# Leds.net
KiCad netlist of a schematic drawn in Altium Designer
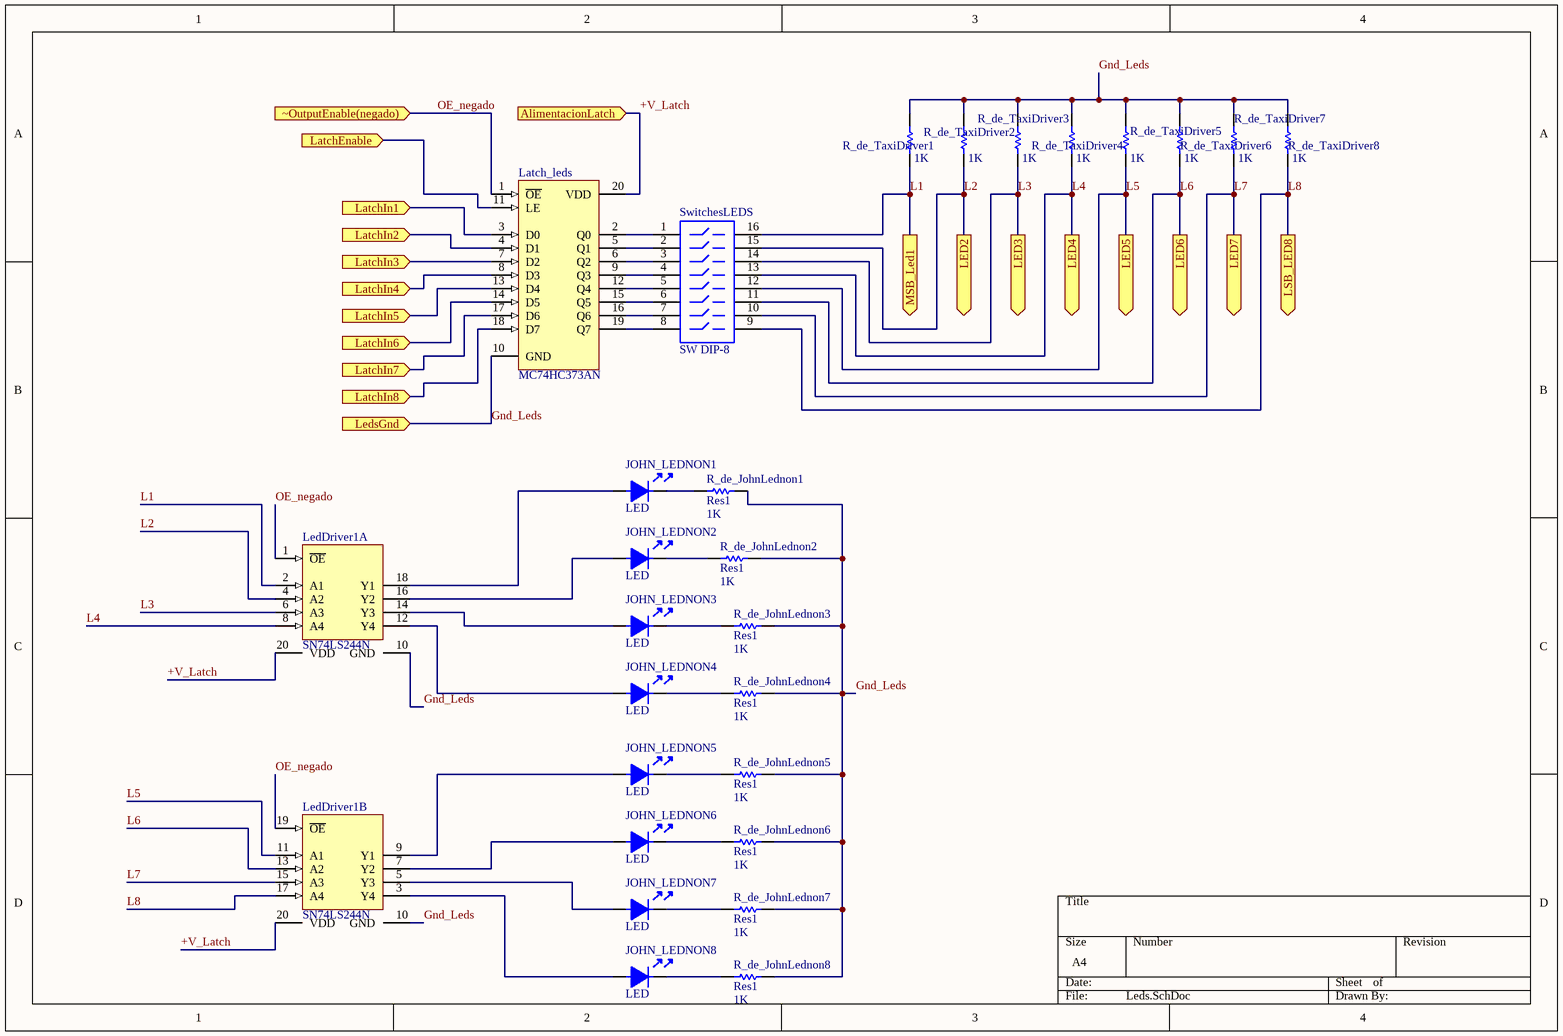
[diagram p0: Leds.SchDoc]

(export (version "E")
  (design (tool "Eeschema 10.0.6"))
  (components
    (comp (ref "JOHN_LEDNON1") (value "LED") (footprint "LED3") (libsource (lib "LIBEBAL") (part "LED")))
    (comp (ref "JOHN_LEDNON2") (value "LED") (footprint "LED3") (libsource (lib "LIBEBAL") (part "LED")))
    (comp (ref "JOHN_LEDNON3") (value "LED") (footprint "LED3") (libsource (lib "LIBEBAL") (part "LED")))
    (comp (ref "JOHN_LEDNON4") (value "LED") (footprint "LED3") (libsource (lib "LIBEBAL") (part "LED")))
    (comp (ref "JOHN_LEDNON5") (value "LED") (footprint "LED3") (libsource (lib "LIBEBAL") (part "LED")))
    (comp (ref "JOHN_LEDNON6") (value "LED") (footprint "LED3") (libsource (lib "LIBEBAL") (part "LED")))
    (comp (ref "JOHN_LEDNON7") (value "LED") (footprint "LED3") (libsource (lib "LIBEBAL") (part "LED")))
    (comp (ref "JOHN_LEDNON8") (value "LED") (footprint "LED3") (libsource (lib "LIBEBAL") (part "LED")))
    (comp (ref "Latch_leds")
      (value "MC74HC373AN")
      (footprint "738-03")
      (description "Octal 3-State Non-Inverting Transparent Latch")
      (fields (field (name "PUBLISHER") "Altium Limited"))
      (libsource (lib "ON Semi Logic Latch") (part "MC74HC373AN"))
    )
    (comp (ref "LedDriver1")
      (value "SN74LS244N")
      (footprint "738-03")
      (description "Octal Buffer/Line Driver with 3-State Outputs")
      (fields (field (name "PUBLISHER") "Altium Limited"))
      (libsource (lib "ON Semi Logic Buffer Line Driver") (part "SN74LS244N"))
    )
    (comp (ref "R_de_JohnLednon1")
      (value "Res1")
      (footprint "AXIAL-0.3")
      (description "Resistor")
      (fields (field (name "ALTIUM_VALUE") "1K") (field (name "PUBLISHER") "Altium Limited"))
      (libsource (lib "Miscellaneous Devices") (part "Res1"))
    )
    (comp (ref "R_de_JohnLednon2")
      (value "Res1")
      (footprint "AXIAL-0.3")
      (description "Resistor")
      (fields (field (name "ALTIUM_VALUE") "1K") (field (name "PUBLISHER") "Altium Limited"))
      (libsource (lib "Miscellaneous Devices") (part "Res1"))
    )
    (comp (ref "R_de_JohnLednon3")
      (value "Res1")
      (footprint "AXIAL-0.3")
      (description "Resistor")
      (fields (field (name "ALTIUM_VALUE") "1K") (field (name "PUBLISHER") "Altium Limited"))
      (libsource (lib "Miscellaneous Devices") (part "Res1"))
    )
    (comp (ref "R_de_JohnLednon4")
      (value "Res1")
      (footprint "AXIAL-0.3")
      (description "Resistor")
      (fields (field (name "ALTIUM_VALUE") "1K") (field (name "PUBLISHER") "Altium Limited"))
      (libsource (lib "Miscellaneous Devices") (part "Res1"))
    )
    (comp (ref "R_de_JohnLednon5")
      (value "Res1")
      (footprint "AXIAL-0.3")
      (description "Resistor")
      (fields (field (name "ALTIUM_VALUE") "1K") (field (name "PUBLISHER") "Altium Limited"))
      (libsource (lib "Miscellaneous Devices") (part "Res1"))
    )
    (comp (ref "R_de_JohnLednon6")
      (value "Res1")
      (footprint "AXIAL-0.3")
      (description "Resistor")
      (fields (field (name "ALTIUM_VALUE") "1K") (field (name "PUBLISHER") "Altium Limited"))
      (libsource (lib "Miscellaneous Devices") (part "Res1"))
    )
    (comp (ref "R_de_JohnLednon7")
      (value "Res1")
      (footprint "AXIAL-0.3")
      (description "Resistor")
      (fields (field (name "ALTIUM_VALUE") "1K") (field (name "PUBLISHER") "Altium Limited"))
      (libsource (lib "Miscellaneous Devices") (part "Res1"))
    )
    (comp (ref "R_de_JohnLednon8")
      (value "Res1")
      (footprint "AXIAL-0.3")
      (description "Resistor")
      (fields (field (name "ALTIUM_VALUE") "1K") (field (name "PUBLISHER") "Altium Limited"))
      (libsource (lib "Miscellaneous Devices") (part "Res1"))
    )
    (comp (ref "R_de_TaxiDriver1")
      (value "1K")
      (footprint "AXIAL-0.3")
      (description "Resistor")
      (fields (field (name "Comment") "Res1") (field (name "PUBLISHER") "Altium Limited"))
      (libsource (lib "Miscellaneous Devices") (part "Res1"))
    )
    (comp (ref "R_de_TaxiDriver2")
      (value "1K")
      (footprint "AXIAL-0.3")
      (description "Resistor")
      (fields (field (name "Comment") "Res1") (field (name "PUBLISHER") "Altium Limited"))
      (libsource (lib "Miscellaneous Devices") (part "Res1"))
    )
    (comp (ref "R_de_TaxiDriver3")
      (value "1K")
      (footprint "AXIAL-0.3")
      (description "Resistor")
      (fields (field (name "Comment") "Res1") (field (name "PUBLISHER") "Altium Limited"))
      (libsource (lib "Miscellaneous Devices") (part "Res1"))
    )
    (comp (ref "R_de_TaxiDriver4")
      (value "1K")
      (footprint "AXIAL-0.3")
      (description "Resistor")
      (fields (field (name "Comment") "Res1") (field (name "PUBLISHER") "Altium Limited"))
      (libsource (lib "Miscellaneous Devices") (part "Res1"))
    )
    (comp (ref "R_de_TaxiDriver5")
      (value "1K")
      (footprint "AXIAL-0.3")
      (description "Resistor")
      (fields (field (name "Comment") "Res1") (field (name "PUBLISHER") "Altium Limited"))
      (libsource (lib "Miscellaneous Devices") (part "Res1"))
    )
    (comp (ref "R_de_TaxiDriver6")
      (value "1K")
      (footprint "AXIAL-0.3")
      (description "Resistor")
      (fields (field (name "Comment") "Res1") (field (name "PUBLISHER") "Altium Limited"))
      (libsource (lib "Miscellaneous Devices") (part "Res1"))
    )
    (comp (ref "R_de_TaxiDriver7")
      (value "1K")
      (footprint "AXIAL-0.3")
      (description "Resistor")
      (fields (field (name "Comment") "Res1") (field (name "PUBLISHER") "Altium Limited"))
      (libsource (lib "Miscellaneous Devices") (part "Res1"))
    )
    (comp (ref "R_de_TaxiDriver8")
      (value "1K")
      (footprint "AXIAL-0.3")
      (description "Resistor")
      (fields (field (name "Comment") "Res1") (field (name "PUBLISHER") "Altium Limited"))
      (libsource (lib "Miscellaneous Devices") (part "Res1"))
    )
    (comp (ref "SwitchesLEDS")
      (value "SW DIP-8")
      (footprint "DIP-16-KEY")
      (description "4009 Series DIP Switch, Raised actuator")
      (fields (field (name "PUBLISHER") "Altium Limited"))
      (libsource (lib "Miscellaneous Devices") (part "SW-DIP8"))
    )
  )
  (nets
    (net (code "1") (name "/L1") (class "Default")
      (node (ref "LedDriver1") (pin "2") (pinfunction "A1_2") (pintype "input"))
      (node (ref "R_de_TaxiDriver1") (pin "1") (pinfunction "1_1") (pintype "passive"))
      (node (ref "SwitchesLEDS") (pin "16") (pinfunction "16_16") (pintype "passive"))
    )
    (net (code "2") (name "/L2") (class "Default")
      (node (ref "LedDriver1") (pin "4") (pinfunction "A2_4") (pintype "input"))
      (node (ref "R_de_TaxiDriver2") (pin "1") (pinfunction "1_1") (pintype "passive"))
      (node (ref "SwitchesLEDS") (pin "15") (pinfunction "15_15") (pintype "passive"))
    )
    (net (code "3") (name "/L3") (class "Default")
      (node (ref "LedDriver1") (pin "6") (pinfunction "A3_6") (pintype "input"))
      (node (ref "R_de_TaxiDriver3") (pin "1") (pinfunction "1_1") (pintype "passive"))
      (node (ref "SwitchesLEDS") (pin "14") (pinfunction "14_14") (pintype "passive"))
    )
    (net (code "4") (name "/L4") (class "Default")
      (node (ref "LedDriver1") (pin "8") (pinfunction "A4_8") (pintype "input"))
      (node (ref "R_de_TaxiDriver4") (pin "1") (pinfunction "1_1") (pintype "passive"))
      (node (ref "SwitchesLEDS") (pin "13") (pinfunction "13_13") (pintype "passive"))
    )
    (net (code "5") (name "/L5") (class "Default")
      (node (ref "LedDriver1") (pin "11") (pinfunction "A1_11") (pintype "input"))
      (node (ref "R_de_TaxiDriver5") (pin "1") (pinfunction "1_1") (pintype "passive"))
      (node (ref "SwitchesLEDS") (pin "12") (pinfunction "12_12") (pintype "passive"))
    )
    (net (code "6") (name "/L6") (class "Default")
      (node (ref "LedDriver1") (pin "13") (pinfunction "A2_13") (pintype "input"))
      (node (ref "R_de_TaxiDriver6") (pin "1") (pinfunction "1_1") (pintype "passive"))
      (node (ref "SwitchesLEDS") (pin "11") (pinfunction "11_11") (pintype "passive"))
    )
    (net (code "7") (name "/L7") (class "Default")
      (node (ref "LedDriver1") (pin "15") (pinfunction "A3_15") (pintype "input"))
      (node (ref "R_de_TaxiDriver7") (pin "1") (pinfunction "1_1") (pintype "passive"))
      (node (ref "SwitchesLEDS") (pin "10") (pinfunction "10_10") (pintype "passive"))
    )
    (net (code "8") (name "/L8") (class "Default")
      (node (ref "LedDriver1") (pin "17") (pinfunction "A4_17") (pintype "input"))
      (node (ref "R_de_TaxiDriver8") (pin "1") (pinfunction "1_1") (pintype "passive"))
      (node (ref "SwitchesLEDS") (pin "9") (pinfunction "9_9") (pintype "passive"))
    )
    (net (code "9") (name "/LatchEnable") (class "Default")
      (node (ref "Latch_leds") (pin "11") (pinfunction "LE_11") (pintype "input"))
    )
    (net (code "10") (name "/LatchIn1") (class "Default")
      (node (ref "Latch_leds") (pin "3") (pinfunction "D0_3") (pintype "input"))
    )
    (net (code "11") (name "/LatchIn2") (class "Default")
      (node (ref "Latch_leds") (pin "4") (pinfunction "D1_4") (pintype "input"))
    )
    (net (code "12") (name "/LatchIn3") (class "Default")
      (node (ref "Latch_leds") (pin "7") (pinfunction "D2_7") (pintype "input"))
    )
    (net (code "13") (name "/LatchIn4") (class "Default")
      (node (ref "Latch_leds") (pin "8") (pinfunction "D3_8") (pintype "input"))
    )
    (net (code "14") (name "/LatchIn5") (class "Default")
      (node (ref "Latch_leds") (pin "13") (pinfunction "D4_13") (pintype "input"))
    )
    (net (code "15") (name "/LatchIn6") (class "Default")
      (node (ref "Latch_leds") (pin "14") (pinfunction "D5_14") (pintype "input"))
    )
    (net (code "16") (name "/LatchIn7") (class "Default")
      (node (ref "Latch_leds") (pin "17") (pinfunction "D6_17") (pintype "input"))
    )
    (net (code "17") (name "/LatchIn8") (class "Default")
      (node (ref "Latch_leds") (pin "18") (pinfunction "D7_18") (pintype "input"))
    )
    (net (code "18") (name "/OE_negado") (class "Default")
      (node (ref "Latch_leds") (pin "1") (pinfunction "~{OE}_1") (pintype "input"))
      (node (ref "LedDriver1") (pin "1") (pinfunction "~{OE}_1") (pintype "input"))
      (node (ref "LedDriver1") (pin "19") (pinfunction "~{OE}_19") (pintype "input"))
    )
    (net (code "19") (name "GND") (class "Default")
      (node (ref "Latch_leds") (pin "10") (pinfunction "GND_10") (pintype "power_in"))
      (node (ref "LedDriver1") (pin "10") (pinfunction "GND_10") (pintype "power_in"))
      (node (ref "R_de_JohnLednon1") (pin "2") (pinfunction "2_2") (pintype "passive"))
      (node (ref "R_de_JohnLednon2") (pin "2") (pinfunction "2_2") (pintype "passive"))
      (node (ref "R_de_JohnLednon3") (pin "2") (pinfunction "2_2") (pintype "passive"))
      (node (ref "R_de_JohnLednon4") (pin "2") (pinfunction "2_2") (pintype "passive"))
      (node (ref "R_de_JohnLednon5") (pin "2") (pinfunction "2_2") (pintype "passive"))
      (node (ref "R_de_JohnLednon6") (pin "2") (pinfunction "2_2") (pintype "passive"))
      (node (ref "R_de_JohnLednon7") (pin "2") (pinfunction "2_2") (pintype "passive"))
      (node (ref "R_de_JohnLednon8") (pin "2") (pinfunction "2_2") (pintype "passive"))
      (node (ref "R_de_TaxiDriver1") (pin "2") (pinfunction "2_2") (pintype "passive"))
      (node (ref "R_de_TaxiDriver2") (pin "2") (pinfunction "2_2") (pintype "passive"))
      (node (ref "R_de_TaxiDriver3") (pin "2") (pinfunction "2_2") (pintype "passive"))
      (node (ref "R_de_TaxiDriver4") (pin "2") (pinfunction "2_2") (pintype "passive"))
      (node (ref "R_de_TaxiDriver5") (pin "2") (pinfunction "2_2") (pintype "passive"))
      (node (ref "R_de_TaxiDriver6") (pin "2") (pinfunction "2_2") (pintype "passive"))
      (node (ref "R_de_TaxiDriver7") (pin "2") (pinfunction "2_2") (pintype "passive"))
      (node (ref "R_de_TaxiDriver8") (pin "2") (pinfunction "2_2") (pintype "passive"))
    )
    (net (code "20") (name "Net-(JOHN_LEDNON1-Pad2)") (class "Default")
      (node (ref "JOHN_LEDNON1") (pin "2") (pinfunction "2_2") (pintype "passive"))
      (node (ref "R_de_JohnLednon1") (pin "1") (pinfunction "1_1") (pintype "passive"))
    )
    (net (code "21") (name "Net-(JOHN_LEDNON2-Pad2)") (class "Default")
      (node (ref "JOHN_LEDNON2") (pin "2") (pinfunction "2_2") (pintype "passive"))
      (node (ref "R_de_JohnLednon2") (pin "1") (pinfunction "1_1") (pintype "passive"))
    )
    (net (code "22") (name "Net-(JOHN_LEDNON3-Pad2)") (class "Default")
      (node (ref "JOHN_LEDNON3") (pin "2") (pinfunction "2_2") (pintype "passive"))
      (node (ref "R_de_JohnLednon3") (pin "1") (pinfunction "1_1") (pintype "passive"))
    )
    (net (code "23") (name "Net-(JOHN_LEDNON4-Pad2)") (class "Default")
      (node (ref "JOHN_LEDNON4") (pin "2") (pinfunction "2_2") (pintype "passive"))
      (node (ref "R_de_JohnLednon4") (pin "1") (pinfunction "1_1") (pintype "passive"))
    )
    (net (code "24") (name "Net-(JOHN_LEDNON5-Pad2)") (class "Default")
      (node (ref "JOHN_LEDNON5") (pin "2") (pinfunction "2_2") (pintype "passive"))
      (node (ref "R_de_JohnLednon5") (pin "1") (pinfunction "1_1") (pintype "passive"))
    )
    (net (code "25") (name "Net-(JOHN_LEDNON6-Pad2)") (class "Default")
      (node (ref "JOHN_LEDNON6") (pin "2") (pinfunction "2_2") (pintype "passive"))
      (node (ref "R_de_JohnLednon6") (pin "1") (pinfunction "1_1") (pintype "passive"))
    )
    (net (code "26") (name "Net-(JOHN_LEDNON7-Pad2)") (class "Default")
      (node (ref "JOHN_LEDNON7") (pin "2") (pinfunction "2_2") (pintype "passive"))
      (node (ref "R_de_JohnLednon7") (pin "1") (pinfunction "1_1") (pintype "passive"))
    )
    (net (code "27") (name "Net-(JOHN_LEDNON8-Pad2)") (class "Default")
      (node (ref "JOHN_LEDNON8") (pin "2") (pinfunction "2_2") (pintype "passive"))
      (node (ref "R_de_JohnLednon8") (pin "1") (pinfunction "1_1") (pintype "passive"))
    )
    (net (code "28") (name "Net-(Latch_leds-Q0)") (class "Default")
      (node (ref "Latch_leds") (pin "2") (pinfunction "Q0_2") (pintype "tri_state"))
      (node (ref "SwitchesLEDS") (pin "1") (pinfunction "1_1") (pintype "passive"))
    )
    (net (code "29") (name "Net-(Latch_leds-Q1)") (class "Default")
      (node (ref "Latch_leds") (pin "5") (pinfunction "Q1_5") (pintype "tri_state"))
      (node (ref "SwitchesLEDS") (pin "2") (pinfunction "2_2") (pintype "passive"))
    )
    (net (code "30") (name "Net-(Latch_leds-Q2)") (class "Default")
      (node (ref "Latch_leds") (pin "6") (pinfunction "Q2_6") (pintype "tri_state"))
      (node (ref "SwitchesLEDS") (pin "3") (pinfunction "3_3") (pintype "passive"))
    )
    (net (code "31") (name "Net-(Latch_leds-Q3)") (class "Default")
      (node (ref "Latch_leds") (pin "9") (pinfunction "Q3_9") (pintype "tri_state"))
      (node (ref "SwitchesLEDS") (pin "4") (pinfunction "4_4") (pintype "passive"))
    )
    (net (code "32") (name "Net-(Latch_leds-Q4)") (class "Default")
      (node (ref "Latch_leds") (pin "12") (pinfunction "Q4_12") (pintype "tri_state"))
      (node (ref "SwitchesLEDS") (pin "5") (pinfunction "5_5") (pintype "passive"))
    )
    (net (code "33") (name "Net-(Latch_leds-Q5)") (class "Default")
      (node (ref "Latch_leds") (pin "15") (pinfunction "Q5_15") (pintype "tri_state"))
      (node (ref "SwitchesLEDS") (pin "6") (pinfunction "6_6") (pintype "passive"))
    )
    (net (code "34") (name "Net-(Latch_leds-Q6)") (class "Default")
      (node (ref "Latch_leds") (pin "16") (pinfunction "Q6_16") (pintype "tri_state"))
      (node (ref "SwitchesLEDS") (pin "7") (pinfunction "7_7") (pintype "passive"))
    )
    (net (code "35") (name "Net-(Latch_leds-Q7)") (class "Default")
      (node (ref "Latch_leds") (pin "19") (pinfunction "Q7_19") (pintype "tri_state"))
      (node (ref "SwitchesLEDS") (pin "8") (pinfunction "8_8") (pintype "passive"))
    )
    (net (code "36") (name "Net-(LedDriver1A-Y1)") (class "Default")
      (node (ref "JOHN_LEDNON1") (pin "1") (pinfunction "1_1") (pintype "passive"))
      (node (ref "LedDriver1") (pin "18") (pinfunction "Y1_18") (pintype "tri_state"))
    )
    (net (code "37") (name "Net-(LedDriver1A-Y2)") (class "Default")
      (node (ref "JOHN_LEDNON2") (pin "1") (pinfunction "1_1") (pintype "passive"))
      (node (ref "LedDriver1") (pin "16") (pinfunction "Y2_16") (pintype "tri_state"))
    )
    (net (code "38") (name "Net-(LedDriver1A-Y3)") (class "Default")
      (node (ref "JOHN_LEDNON3") (pin "1") (pinfunction "1_1") (pintype "passive"))
      (node (ref "LedDriver1") (pin "14") (pinfunction "Y3_14") (pintype "tri_state"))
    )
    (net (code "39") (name "Net-(LedDriver1A-Y4)") (class "Default")
      (node (ref "JOHN_LEDNON4") (pin "1") (pinfunction "1_1") (pintype "passive"))
      (node (ref "LedDriver1") (pin "12") (pinfunction "Y4_12") (pintype "tri_state"))
    )
    (net (code "40") (name "Net-(LedDriver1B-Y1)") (class "Default")
      (node (ref "JOHN_LEDNON5") (pin "1") (pinfunction "1_1") (pintype "passive"))
      (node (ref "LedDriver1") (pin "9") (pinfunction "Y1_9") (pintype "tri_state"))
    )
    (net (code "41") (name "Net-(LedDriver1B-Y2)") (class "Default")
      (node (ref "JOHN_LEDNON6") (pin "1") (pinfunction "1_1") (pintype "passive"))
      (node (ref "LedDriver1") (pin "7") (pinfunction "Y2_7") (pintype "tri_state"))
    )
    (net (code "42") (name "Net-(LedDriver1B-Y3)") (class "Default")
      (node (ref "JOHN_LEDNON7") (pin "1") (pinfunction "1_1") (pintype "passive"))
      (node (ref "LedDriver1") (pin "5") (pinfunction "Y3_5") (pintype "tri_state"))
    )
    (net (code "43") (name "Net-(LedDriver1B-Y4)") (class "Default")
      (node (ref "JOHN_LEDNON8") (pin "1") (pinfunction "1_1") (pintype "passive"))
      (node (ref "LedDriver1") (pin "3") (pinfunction "Y4_3") (pintype "tri_state"))
    )
    (net (code "44") (name "VDD") (class "Default")
      (node (ref "Latch_leds") (pin "20") (pinfunction "VDD_20") (pintype "power_in"))
      (node (ref "LedDriver1") (pin "20") (pinfunction "VDD_20") (pintype "power_in"))
    )
  )
)
